# REL_IRF_MEZ.net
KiCad netlist of a schematic drawn in Altium Designer
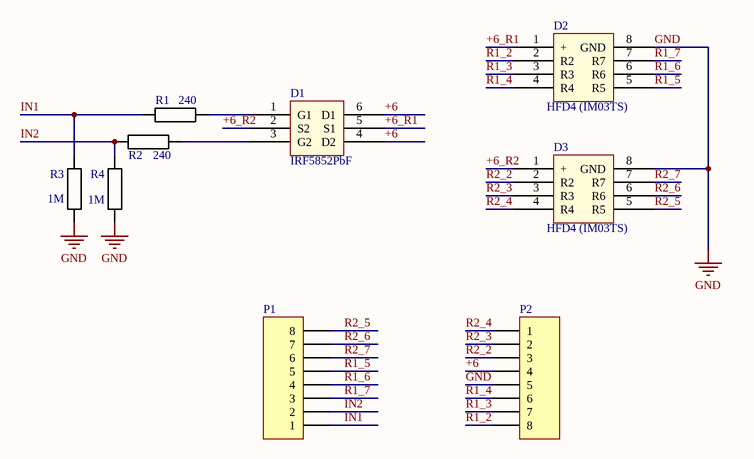
[diagram p0: REL_IRF_MEZ.SchDoc]

(export (version "E")
  (design (tool "Eeschema 10.0.6"))
  (components
    (comp (ref "D1")
      (value "IRF5852PbF")
      (footprint "msp_Active:IRF5852PbF")
      (libsource (lib "msp_SchLib") (part "IRF5852PbF"))
    )
    (comp (ref "D2")
      (value "HFD4 (IM03TS)")
      (footprint "msp_Active:HFD4 (IM03TS)")
      (libsource (lib "msp_SchLib") (part "HFD4 (IM03TS)"))
    )
    (comp (ref "D3")
      (value "HFD4 (IM03TS)")
      (footprint "msp_Active:HFD4 (IM03TS)")
      (libsource (lib "msp_SchLib") (part "HFD4 (IM03TS)"))
    )
    (comp (ref "P1")
      (value "Header 8")
      (footprint "HDR1X8")
      (description "Header, 8-Pin")
      (fields (field (name "PUBLISHER") "Altium Limited"))
      (libsource (lib "Miscellaneous Connectors") (part "Header 8"))
    )
    (comp (ref "P2")
      (value "Header 8")
      (footprint "HDR1X8")
      (description "Header, 8-Pin")
      (fields (field (name "PUBLISHER") "Altium Limited"))
      (libsource (lib "") (part "Header 8_1"))
    )
    (comp (ref "R1")
      (value "240")
      (footprint "aab_Passive:RES_1206")
      (libsource (lib "aab_Schlib") (part "RES"))
    )
    (comp (ref "R2")
      (value "240")
      (footprint "aab_Passive:RES_1206")
      (libsource (lib "aab_Schlib") (part "RES"))
    )
    (comp (ref "R3")
      (value "1М")
      (footprint "aab_Passive:RES_1206")
      (libsource (lib "aab_Schlib") (part "RES"))
    )
    (comp (ref "R4")
      (value "1М")
      (footprint "aab_Passive:RES_1206")
      (libsource (lib "aab_Schlib") (part "RES"))
    )
  )
  (nets
    (net (code "1") (name "/+6") (class "Default")
      (node (ref "D1") (pin "4") (pinfunction "D2_4") (pintype "passive"))
      (node (ref "D1") (pin "6") (pinfunction "D1_6") (pintype "passive"))
      (node (ref "P2") (pin "4") (pinfunction "4_4") (pintype "passive"))
    )
    (net (code "2") (name "/+6_R1") (class "Default")
      (node (ref "D1") (pin "5") (pinfunction "S1_5") (pintype "passive"))
      (node (ref "D2") (pin "1") (pinfunction "+_1") (pintype "passive"))
    )
    (net (code "3") (name "/+6_R2") (class "Default")
      (node (ref "D1") (pin "2") (pinfunction "S2_2") (pintype "passive"))
      (node (ref "D3") (pin "1") (pinfunction "+_1") (pintype "passive"))
    )
    (net (code "4") (name "/IN1") (class "Default")
      (node (ref "P1") (pin "1") (pinfunction "1_1") (pintype "passive"))
      (node (ref "R1") (pin "1") (pinfunction "1_1") (pintype "passive"))
      (node (ref "R3") (pin "1") (pinfunction "1_1") (pintype "passive"))
    )
    (net (code "5") (name "/IN2") (class "Default")
      (node (ref "P1") (pin "2") (pinfunction "2_2") (pintype "passive"))
      (node (ref "R2") (pin "1") (pinfunction "1_1") (pintype "passive"))
      (node (ref "R4") (pin "2") (pinfunction "2_2") (pintype "passive"))
    )
    (net (code "6") (name "/R1_2") (class "Default")
      (node (ref "D2") (pin "2") (pinfunction "R2_2") (pintype "passive"))
      (node (ref "P2") (pin "8") (pinfunction "8_8") (pintype "passive"))
    )
    (net (code "7") (name "/R1_3") (class "Default")
      (node (ref "D2") (pin "3") (pinfunction "R3_3") (pintype "passive"))
      (node (ref "P2") (pin "7") (pinfunction "7_7") (pintype "passive"))
    )
    (net (code "8") (name "/R1_4") (class "Default")
      (node (ref "D2") (pin "4") (pinfunction "R4_4") (pintype "passive"))
      (node (ref "P2") (pin "6") (pinfunction "6_6") (pintype "passive"))
    )
    (net (code "9") (name "/R1_5") (class "Default")
      (node (ref "D2") (pin "5") (pinfunction "R5_5") (pintype "passive"))
      (node (ref "P1") (pin "5") (pinfunction "5_5") (pintype "passive"))
    )
    (net (code "10") (name "/R1_6") (class "Default")
      (node (ref "D2") (pin "6") (pinfunction "R6_6") (pintype "passive"))
      (node (ref "P1") (pin "4") (pinfunction "4_4") (pintype "passive"))
    )
    (net (code "11") (name "/R1_7") (class "Default")
      (node (ref "D2") (pin "7") (pinfunction "R7_7") (pintype "passive"))
      (node (ref "P1") (pin "3") (pinfunction "3_3") (pintype "passive"))
    )
    (net (code "12") (name "/R2_2") (class "Default")
      (node (ref "D3") (pin "2") (pinfunction "R2_2") (pintype "passive"))
      (node (ref "P2") (pin "3") (pinfunction "3_3") (pintype "passive"))
    )
    (net (code "13") (name "/R2_3") (class "Default")
      (node (ref "D3") (pin "3") (pinfunction "R3_3") (pintype "passive"))
      (node (ref "P2") (pin "2") (pinfunction "2_2") (pintype "passive"))
    )
    (net (code "14") (name "/R2_4") (class "Default")
      (node (ref "D3") (pin "4") (pinfunction "R4_4") (pintype "passive"))
      (node (ref "P2") (pin "1") (pinfunction "1_1") (pintype "passive"))
    )
    (net (code "15") (name "/R2_5") (class "Default")
      (node (ref "D3") (pin "5") (pinfunction "R5_5") (pintype "passive"))
      (node (ref "P1") (pin "8") (pinfunction "8_8") (pintype "passive"))
    )
    (net (code "16") (name "/R2_6") (class "Default")
      (node (ref "D3") (pin "6") (pinfunction "R6_6") (pintype "passive"))
      (node (ref "P1") (pin "7") (pinfunction "7_7") (pintype "passive"))
    )
    (net (code "17") (name "/R2_7") (class "Default")
      (node (ref "D3") (pin "7") (pinfunction "R7_7") (pintype "passive"))
      (node (ref "P1") (pin "6") (pinfunction "6_6") (pintype "passive"))
    )
    (net (code "18") (name "GND") (class "Default")
      (node (ref "D2") (pin "8") (pinfunction "GND_8") (pintype "passive"))
      (node (ref "D3") (pin "8") (pinfunction "GND_8") (pintype "passive"))
      (node (ref "P2") (pin "5") (pinfunction "5_5") (pintype "passive"))
      (node (ref "R3") (pin "2") (pinfunction "2_2") (pintype "passive"))
      (node (ref "R4") (pin "1") (pinfunction "1_1") (pintype "passive"))
    )
    (net (code "19") (name "Net-(D1-G1)") (class "Default")
      (node (ref "D1") (pin "1") (pinfunction "G1_1") (pintype "passive"))
      (node (ref "R1") (pin "2") (pinfunction "2_2") (pintype "passive"))
    )
    (net (code "20") (name "Net-(D1-G2)") (class "Default")
      (node (ref "D1") (pin "3") (pinfunction "G2_3") (pintype "passive"))
      (node (ref "R2") (pin "2") (pinfunction "2_2") (pintype "passive"))
    )
  )
)
